# PIC32MK.net
KiCad netlist of a schematic drawn in Altium Designer
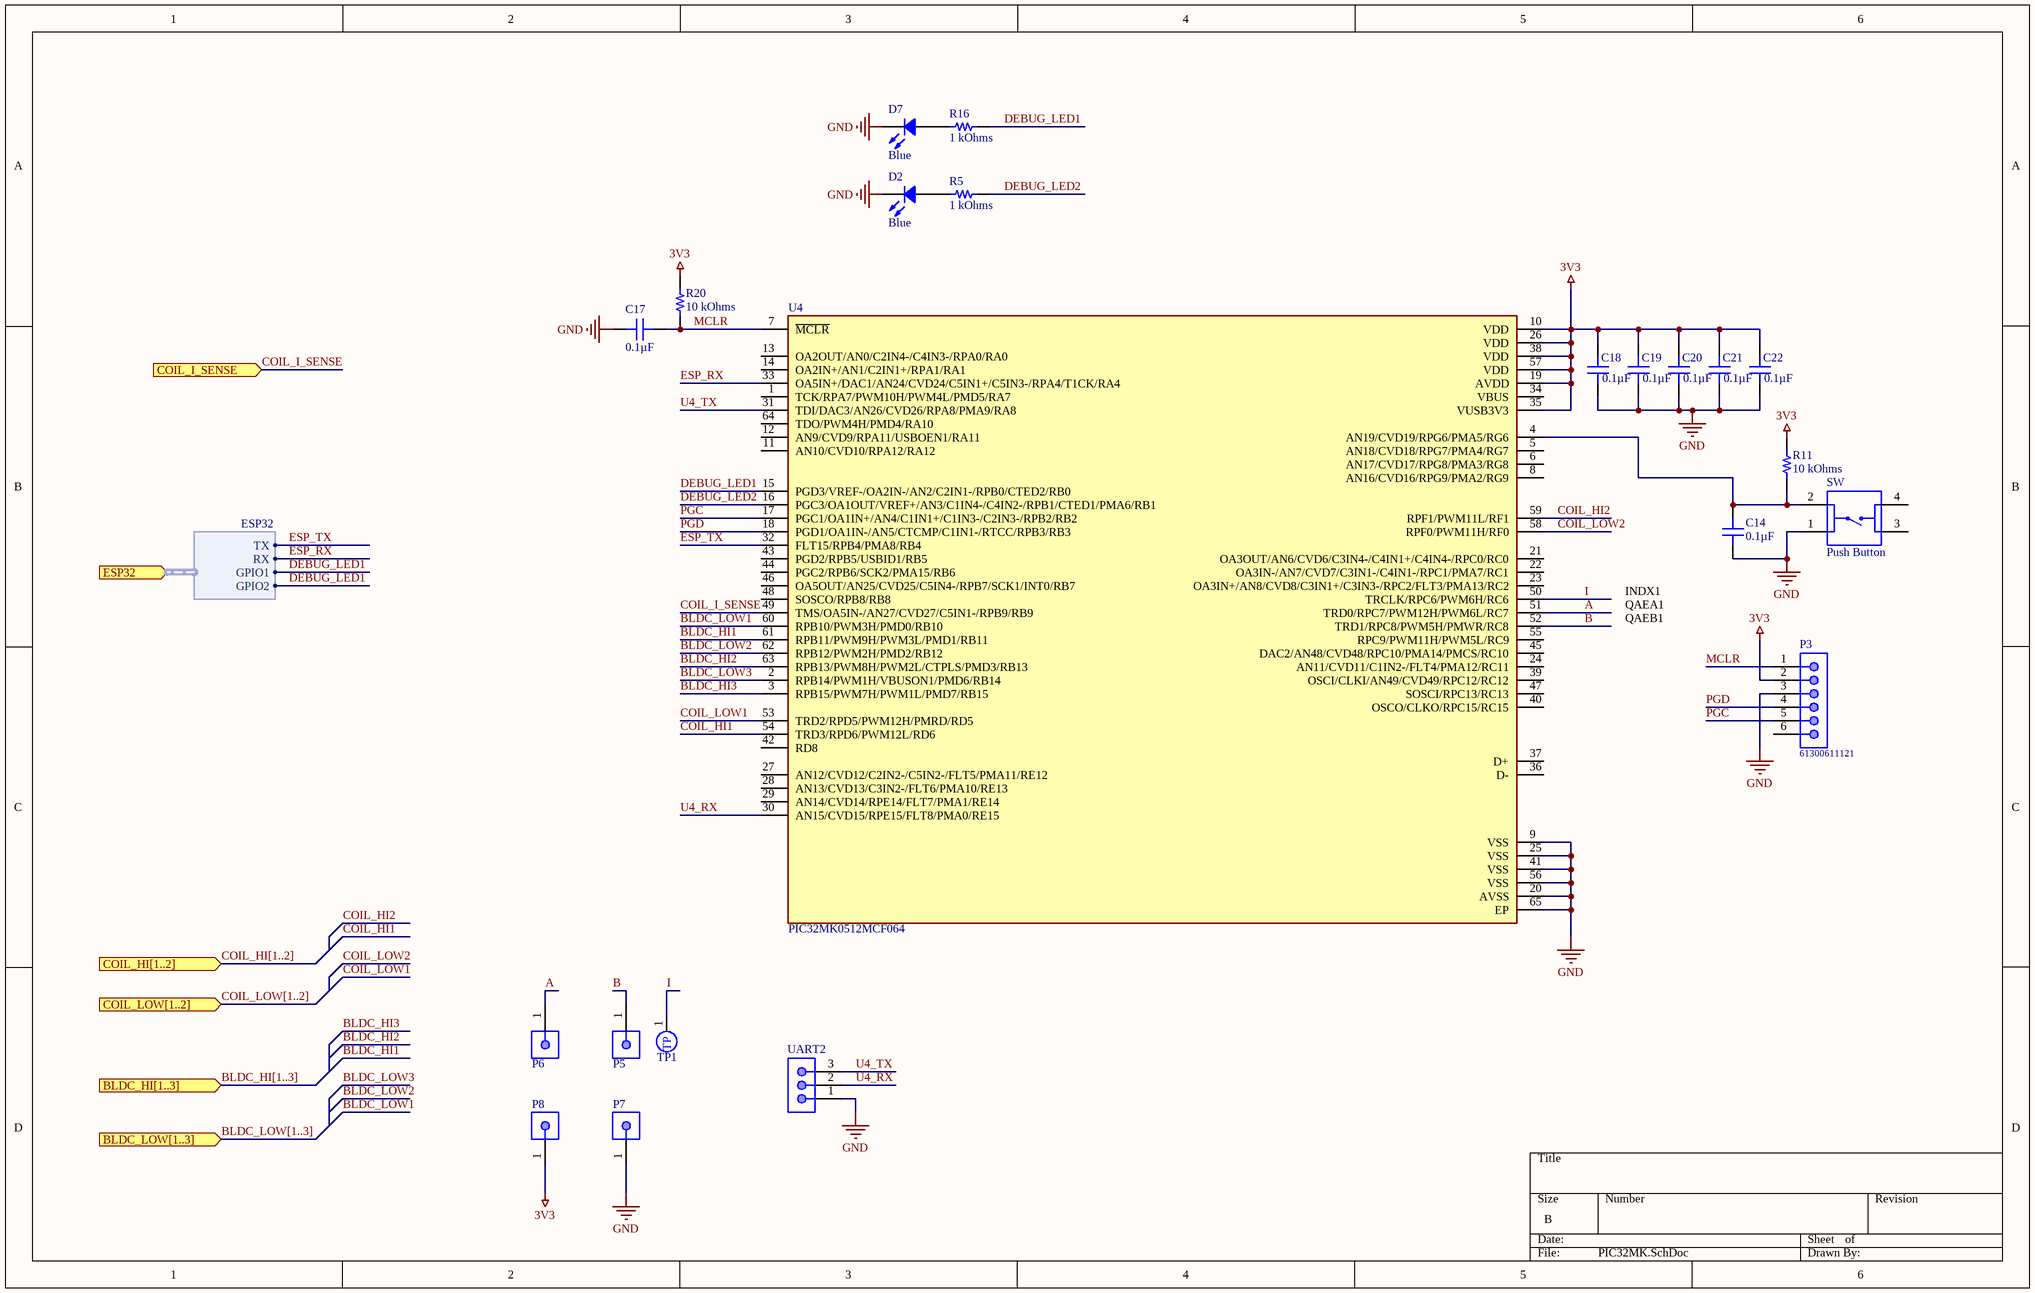
[diagram p0: PIC32MK.SchDoc]

(export (version "E")
  (design (tool "Eeschema 10.0.6"))
  (components
    (comp (ref "C14")
      (value "0.1µF")
      (footprint "CAP 0603_1608")
      (description "CAP CER 0.1UF 100V 0603 EPOXY")
      (fields
        (field (name "PART NUMBER") "GCG188R92A104KA03D")
        (field (name "MANUFACTURER") "Murata Electronics")
      )
      (libsource (lib "Celestial Altium Library - altium_library") (part "Capacitor"))
    )
    (comp (ref "C17")
      (value "0.1µF")
      (footprint "CAP 0603_1608")
      (description "CAP CER 0.1UF 100V 0603 EPOXY")
      (fields
        (field (name "PART NUMBER") "GCG188R92A104KA03D")
        (field (name "MANUFACTURER") "Murata Electronics")
      )
      (libsource (lib "Celestial Altium Library - altium_library") (part "Capacitor"))
    )
    (comp (ref "C18")
      (value "0.1µF")
      (footprint "CAP 0603_1608")
      (description "CAP CER 0.1UF 100V 0603 EPOXY")
      (fields
        (field (name "PART NUMBER") "GCG188R92A104KA03D")
        (field (name "MANUFACTURER") "Murata Electronics")
      )
      (libsource (lib "Celestial Altium Library - altium_library") (part "Capacitor"))
    )
    (comp (ref "C19")
      (value "0.1µF")
      (footprint "CAP 0603_1608")
      (description "CAP CER 0.1UF 100V 0603 EPOXY")
      (fields
        (field (name "PART NUMBER") "GCG188R92A104KA03D")
        (field (name "MANUFACTURER") "Murata Electronics")
      )
      (libsource (lib "Celestial Altium Library - altium_library") (part "Capacitor"))
    )
    (comp (ref "C20")
      (value "0.1µF")
      (footprint "CAP 0603_1608")
      (description "CAP CER 0.1UF 100V 0603 EPOXY")
      (fields
        (field (name "PART NUMBER") "GCG188R92A104KA03D")
        (field (name "MANUFACTURER") "Murata Electronics")
      )
      (libsource (lib "Celestial Altium Library - altium_library") (part "Capacitor"))
    )
    (comp (ref "C21")
      (value "0.1µF")
      (footprint "CAP 0603_1608")
      (description "CAP CER 0.1UF 100V 0603 EPOXY")
      (fields
        (field (name "PART NUMBER") "GCG188R92A104KA03D")
        (field (name "MANUFACTURER") "Murata Electronics")
      )
      (libsource (lib "Celestial Altium Library - altium_library") (part "Capacitor"))
    )
    (comp (ref "C22")
      (value "0.1µF")
      (footprint "CAP 0603_1608")
      (description "CAP CER 0.1UF 100V 0603 EPOXY")
      (fields
        (field (name "PART NUMBER") "GCG188R92A104KA03D")
        (field (name "MANUFACTURER") "Murata Electronics")
      )
      (libsource (lib "Celestial Altium Library - altium_library") (part "Capacitor"))
    )
    (comp (ref "D2")
      (value "Blue")
      (footprint "LED 0603_1608 GREEN")
      (description "Blue LED")
      (fields (field (name "PART NUMBER") "XZCDGK53W-8VF") (field (name "MANUFACTURER") "SunLED"))
      (libsource (lib "Celestial Altium Library - altium_library") (part "LED"))
    )
    (comp (ref "D7")
      (value "Blue")
      (footprint "LED 0603_1608 GREEN")
      (description "Blue LED")
      (fields (field (name "PART NUMBER") "XZCDGK53W-8VF") (field (name "MANUFACTURER") "SunLED"))
      (libsource (lib "Celestial Altium Library - altium_library") (part "LED"))
    )
    (comp (ref "P3")
      (value "61300611121")
      (footprint "61300611121")
      (description "WR-PHD Pin Header, THT, pitch 2.54mm, Single Row, Vertical, 6p")
      (fields (field (name "MANUFACTURER") "Wurth Elektronik"))
      (libsource (lib "Altium_WR-PHD") (part "61300611121"))
    )
    (comp (ref "P5")
      (value "61300111121")
      (footprint "61300111121")
      (description "WR-PHD Pin Header, THT, pitch 2.54mm, Single Row, Vertical, 1p")
      (fields (field (name "MANUFACTURER") "Wurth Elektronik"))
      (libsource (lib "Altium_WR-PHD") (part "61300111121"))
    )
    (comp (ref "P6")
      (value "61300111121")
      (footprint "61300111121")
      (description "WR-PHD Pin Header, THT, pitch 2.54mm, Single Row, Vertical, 1p")
      (fields (field (name "MANUFACTURER") "Wurth Elektronik"))
      (libsource (lib "Altium_WR-PHD") (part "61300111121"))
    )
    (comp (ref "P7")
      (value "61300111121")
      (footprint "61300111121")
      (description "WR-PHD Pin Header, THT, pitch 2.54mm, Single Row, Vertical, 1p")
      (fields (field (name "MANUFACTURER") "Wurth Elektronik"))
      (libsource (lib "Altium_WR-PHD") (part "61300111121"))
    )
    (comp (ref "P8")
      (value "61300111121")
      (footprint "61300111121")
      (description "WR-PHD Pin Header, THT, pitch 2.54mm, Single Row, Vertical, 1p")
      (fields (field (name "MANUFACTURER") "Wurth Elektronik"))
      (libsource (lib "Altium_WR-PHD") (part "61300111121"))
    )
    (comp (ref "R5")
      (value "1 kOhms")
      (footprint "RES 0603_1608")
      (description "RES 1K OHM 0.5% 1/10W 0603")
      (fields
        (field (name "PART NUMBER") "RNCF0603DTE1K00")
        (field (name "MANUFACTURER") "Stackpole Electronics Inc")
      )
      (libsource (lib "Celestial Altium Library - altium_library") (part "Resistor"))
    )
    (comp (ref "R11")
      (value "10 kOhms")
      (footprint "RES 0603_1608")
      (description "RES 10K OHM 0.1% 1/16W 0603")
      (fields
        (field (name "PART NUMBER") "RNCS0603BKE10K0")
        (field (name "MANUFACTURER") "Stackpole Electronics Inc")
      )
      (libsource (lib "Celestial Altium Library - altium_library") (part "Resistor"))
    )
    (comp (ref "R16")
      (value "1 kOhms")
      (footprint "RES 0603_1608")
      (description "RES 1K OHM 0.5% 1/10W 0603")
      (fields
        (field (name "PART NUMBER") "RNCF0603DTE1K00")
        (field (name "MANUFACTURER") "Stackpole Electronics Inc")
      )
      (libsource (lib "Celestial Altium Library - altium_library") (part "Resistor"))
    )
    (comp (ref "R20")
      (value "10 kOhms")
      (footprint "RES 0603_1608")
      (description "RES 10K OHM 0.1% 1/16W 0603")
      (fields
        (field (name "PART NUMBER") "RNCS0603BKE10K0")
        (field (name "MANUFACTURER") "Stackpole Electronics Inc")
      )
      (libsource (lib "Celestial Altium Library - altium_library") (part "Resistor"))
    )
    (comp (ref "SW")
      (value "Push Button")
      (footprint "PushButton")
      (description "50 mA SPST Round Actuator 160 Gram Force Tactile Pushbutton Switch")
      (fields (field (name "MP") "1825910-2") (field (name "MF") "TE Connectivity"))
      (libsource (lib "IC") (part "Push Button"))
    )
    (comp (ref "TP1")
      (value "TP")
      (footprint "TP")
      (description "Test point")
      (libsource (lib "IC") (part "TP"))
    )
    (comp (ref "U4")
      (value "PIC32MK0512MCF064")
      (footprint "QFN50P900X900X100-65N")
      (description "PIC32MK Microcontroller IC 32-Bit 120MHz 1MB _1M x 8_ FLASH 64-TQFP _10x10_")
      (fields
        (field (name "MP") "PIC32MK1024MCF064-I/PT")
        (field (name "DIGI-KEY_PART_NUMBER") "PIC32MK1024MCF064-I/PT-ND")
      )
      (libsource (lib "IC") (part "PIC32MK0512MCF064"))
    )
    (comp (ref "UART2")
      (value "3 pin 2mm JST Male")
      (footprint "3pin - 2mm header")
      (libsource (lib "IC") (part "3 pin 2mm JST Male"))
    )
  )
  (nets
    (net (code "2") (name "/A") (class "Default")
      (node (ref "P6") (pin "1") (pinfunction "1_1") (pintype "passive"))
      (node (ref "U4") (pin "51") (pinfunction "TRD0/RPC7/PWM12H/PWM6L/RC7_51") (pintype "passive"))
    )
    (net (code "3") (name "/B") (class "Default")
      (node (ref "P5") (pin "1") (pinfunction "1_1") (pintype "passive"))
      (node (ref "U4") (pin "52") (pinfunction "TRD1/RPC8/PWM5H/PMWR/RC8_52") (pintype "passive"))
    )
    (net (code "4") (name "/BLDC_HI1") (class "Default")
      (node (ref "U4") (pin "61") (pinfunction "RPB11/PWM9H/PWM3L/PMD1/RB11_61") (pintype "passive"))
    )
    (net (code "5") (name "/BLDC_HI2") (class "Default")
      (node (ref "U4") (pin "63") (pinfunction "RPB13/PWM8H/PWM2L/CTPLS/PMD3/RB13_63") (pintype "passive"))
    )
    (net (code "6") (name "/BLDC_HI3") (class "Default")
      (node (ref "U4") (pin "3") (pinfunction "RPB15/PWM7H/PWM1L/PMD7/RB15_3") (pintype "passive"))
    )
    (net (code "8") (name "/BLDC_LOW1") (class "Default")
      (node (ref "U4") (pin "60") (pinfunction "RPB10/PWM3H/PMD0/RB10_60") (pintype "passive"))
    )
    (net (code "9") (name "/BLDC_LOW2") (class "Default")
      (node (ref "U4") (pin "62") (pinfunction "RPB12/PWM2H/PMD2/RB12_62") (pintype "passive"))
    )
    (net (code "10") (name "/BLDC_LOW3") (class "Default")
      (node (ref "U4") (pin "2") (pinfunction "RPB14/PWM1H/VBUSON1/PMD6/RB14_2") (pintype "passive"))
    )
    (net (code "12") (name "/COIL_HI1") (class "Default")
      (node (ref "U4") (pin "54") (pinfunction "TRD3/RPD6/PWM12L/RD6_54") (pintype "passive"))
    )
    (net (code "13") (name "/COIL_HI2") (class "Default")
      (node (ref "U4") (pin "59") (pinfunction "RPF1/PWM11L/RF1_59") (pintype "passive"))
    )
    (net (code "15") (name "/COIL_I_SENSE") (class "Default")
      (node (ref "U4") (pin "49") (pinfunction "TMS/OA5IN-/AN27/CVD27/C5IN1-/RPB9/RB9_49") (pintype "passive"))
    )
    (net (code "16") (name "/COIL_LOW1") (class "Default")
      (node (ref "U4") (pin "53") (pinfunction "TRD2/RPD5/PWM12H/PMRD/RD5_53") (pintype "passive"))
    )
    (net (code "17") (name "/COIL_LOW2") (class "Default")
      (node (ref "U4") (pin "58") (pinfunction "RPF0/PWM11H/RF0_58") (pintype "passive"))
    )
    (net (code "19") (name "/DEBUG_LED1") (class "Default")
      (node (ref "R16") (pin "1") (pinfunction "1_1") (pintype "passive"))
      (node (ref "U4") (pin "15") (pinfunction "PGD3/VREF-/OA2IN-/AN2/C2IN1-/RPB0/CTED2/RB0_15") (pintype "passive"))
    )
    (net (code "20") (name "/DEBUG_LED2") (class "Default")
      (node (ref "R5") (pin "1") (pinfunction "1_1") (pintype "passive"))
      (node (ref "U4") (pin "16") (pinfunction "PGC3/OA1OUT/VREF+/AN3/C1IN4-/C4IN2-/RPB1/CTED1/PMA6/RB1_16") (pintype "passive"))
    )
    (net (code "21") (name "/ESP_RX") (class "Default")
      (node (ref "U4") (pin "33") (pinfunction "OA5IN+/DAC1/AN24/CVD24/C5IN1+/C5IN3-/RPA4/T1CK/RA4_33") (pintype "passive"))
    )
    (net (code "22") (name "/ESP_TX") (class "Default")
      (node (ref "U4") (pin "32") (pinfunction "FLT15/RPB4/PMA8/RB4_32") (pintype "passive"))
    )
    (net (code "23") (name "/I") (class "Default")
      (node (ref "TP1") (pin "1") (pinfunction "TP_1") (pintype "passive"))
      (node (ref "U4") (pin "50") (pinfunction "TRCLK/RPC6/PWM6H/RC6_50") (pintype "passive"))
    )
    (net (code "24") (name "/MCLR") (class "Default")
      (node (ref "C17") (pin "1") (pinfunction "1_1") (pintype "passive"))
      (node (ref "P3") (pin "1") (pinfunction "1_1") (pintype "passive"))
      (node (ref "R20") (pin "1") (pinfunction "1_1") (pintype "passive"))
      (node (ref "U4") (pin "7") (pinfunction "~{MCLR}_7") (pintype "passive"))
    )
    (net (code "25") (name "/PGC") (class "Default")
      (node (ref "P3") (pin "5") (pinfunction "5_5") (pintype "passive"))
      (node (ref "U4") (pin "17") (pinfunction "PGC1/OA1IN+/AN4/C1IN1+/C1IN3-/C2IN3-/RPB2/RB2_17") (pintype "passive"))
    )
    (net (code "26") (name "/PGD") (class "Default")
      (node (ref "P3") (pin "4") (pinfunction "4_4") (pintype "passive"))
      (node (ref "U4") (pin "18") (pinfunction "PGD1/OA1IN-/AN5/CTCMP/C1IN1-/RTCC/RPB3/RB3_18") (pintype "passive"))
    )
    (net (code "27") (name "/U4_RX") (class "Default")
      (node (ref "U4") (pin "30") (pinfunction "AN15/CVD15/RPE15/FLT8/PMA0/RE15_30") (pintype "passive"))
      (node (ref "UART2") (pin "2") (pinfunction "2_2") (pintype "passive"))
    )
    (net (code "28") (name "/U4_TX") (class "Default")
      (node (ref "U4") (pin "31") (pinfunction "TDI/DAC3/AN26/CVD26/RPA8/PMA9/RA8_31") (pintype "passive"))
      (node (ref "UART2") (pin "3") (pinfunction "3_3") (pintype "passive"))
    )
    (net (code "30") (name "3V3") (class "Default")
      (node (ref "C18") (pin "1") (pinfunction "1_1") (pintype "passive"))
      (node (ref "C19") (pin "1") (pinfunction "1_1") (pintype "passive"))
      (node (ref "C20") (pin "1") (pinfunction "1_1") (pintype "passive"))
      (node (ref "C21") (pin "1") (pinfunction "1_1") (pintype "passive"))
      (node (ref "C22") (pin "1") (pinfunction "1_1") (pintype "passive"))
      (node (ref "P3") (pin "2") (pinfunction "2_2") (pintype "passive"))
      (node (ref "P8") (pin "1") (pinfunction "1_1") (pintype "passive"))
      (node (ref "R11") (pin "2") (pinfunction "2_2") (pintype "passive"))
      (node (ref "R20") (pin "2") (pinfunction "2_2") (pintype "passive"))
      (node (ref "U4") (pin "10") (pinfunction "VDD_10") (pintype "power_in"))
      (node (ref "U4") (pin "19") (pinfunction "AVDD_19") (pintype "power_in"))
      (node (ref "U4") (pin "26") (pinfunction "VDD_26") (pintype "power_in"))
      (node (ref "U4") (pin "35") (pinfunction "VUSB3V3_35") (pintype "passive"))
      (node (ref "U4") (pin "38") (pinfunction "VDD_38") (pintype "power_in"))
      (node (ref "U4") (pin "57") (pinfunction "VDD_57") (pintype "power_in"))
    )
    (net (code "31") (name "GND") (class "Default")
      (node (ref "C14") (pin "2") (pinfunction "2_2") (pintype "passive"))
      (node (ref "C17") (pin "2") (pinfunction "2_2") (pintype "passive"))
      (node (ref "C18") (pin "2") (pinfunction "2_2") (pintype "passive"))
      (node (ref "C19") (pin "2") (pinfunction "2_2") (pintype "passive"))
      (node (ref "C20") (pin "2") (pinfunction "2_2") (pintype "passive"))
      (node (ref "C21") (pin "2") (pinfunction "2_2") (pintype "passive"))
      (node (ref "C22") (pin "2") (pinfunction "2_2") (pintype "passive"))
      (node (ref "D2") (pin "2") (pinfunction "2_2") (pintype "passive"))
      (node (ref "D7") (pin "2") (pinfunction "2_2") (pintype "passive"))
      (node (ref "P3") (pin "3") (pinfunction "3_3") (pintype "passive"))
      (node (ref "P7") (pin "1") (pinfunction "1_1") (pintype "passive"))
      (node (ref "SW") (pin "1") (pinfunction "1_1") (pintype "passive"))
      (node (ref "U4") (pin "20") (pinfunction "AVSS_20") (pintype "power_in"))
      (node (ref "U4") (pin "25") (pinfunction "VSS_25") (pintype "power_in"))
      (node (ref "U4") (pin "41") (pinfunction "VSS_41") (pintype "power_in"))
      (node (ref "U4") (pin "56") (pinfunction "VSS_56") (pintype "power_in"))
      (node (ref "U4") (pin "65") (pinfunction "EP_65") (pintype "power_in"))
      (node (ref "U4") (pin "9") (pinfunction "VSS_9") (pintype "power_in"))
      (node (ref "UART2") (pin "1") (pinfunction "1_1") (pintype "passive"))
    )
    (net (code "32") (name "Net-(D2-Pad1)") (class "Default")
      (node (ref "D2") (pin "1") (pinfunction "1_1") (pintype "passive"))
      (node (ref "R5") (pin "2") (pinfunction "2_2") (pintype "passive"))
    )
    (net (code "33") (name "Net-(D7-Pad1)") (class "Default")
      (node (ref "D7") (pin "1") (pinfunction "1_1") (pintype "passive"))
      (node (ref "R16") (pin "2") (pinfunction "2_2") (pintype "passive"))
    )
    (net (code "34") (name "Net-(U4-AN19{slash}CVD19{slash}RPG6{slash}PMA5{slash}RG6)") (class "Default")
      (node (ref "C14") (pin "1") (pinfunction "1_1") (pintype "passive"))
      (node (ref "R11") (pin "1") (pinfunction "1_1") (pintype "passive"))
      (node (ref "SW") (pin "2") (pinfunction "2_2") (pintype "passive"))
      (node (ref "U4") (pin "4") (pinfunction "AN19/CVD19/RPG6/PMA5/RG6_4") (pintype "passive"))
    )
    (net (code "35") (name "unconnected-(P3-Pad6)") (class "Default")
      (node (ref "P3") (pin "6") (pinfunction "6_6") (pintype "passive"))
    )
    (net (code "36") (name "unconnected-(SW-Pad3)") (class "Default")
      (node (ref "SW") (pin "3") (pinfunction "3_3") (pintype "passive"))
    )
    (net (code "37") (name "unconnected-(SW-Pad4)") (class "Default")
      (node (ref "SW") (pin "4") (pinfunction "4_4") (pintype "passive"))
    )
    (net (code "38") (name "unconnected-(U4-AN9{slash}CVD9{slash}RPA11{slash}USBOEN1{slash}RA11-Pad12)") (class "Default")
      (node (ref "U4") (pin "12") (pinfunction "AN9/CVD9/RPA11/USBOEN1/RA11_12") (pintype "passive"))
    )
    (net (code "39") (name "unconnected-(U4-AN10{slash}CVD10{slash}RPA12{slash}RA12-Pad11)") (class "Default")
      (node (ref "U4") (pin "11") (pinfunction "AN10/CVD10/RPA12/RA12_11") (pintype "passive"))
    )
    (net (code "40") (name "unconnected-(U4-AN11{slash}CVD11{slash}C1IN2-{slash}FLT4{slash}PMA12{slash}RC11-Pad24)") (class "Default")
      (node (ref "U4") (pin "24") (pinfunction "AN11/CVD11/C1IN2-/FLT4/PMA12/RC11_24") (pintype "passive"))
    )
    (net (code "41") (name "unconnected-(U4-AN12{slash}CVD12{slash}C2IN2-{slash}C5IN2-{slash}FLT5{slash}PMA11{slash}RE12-Pad27)") (class "Default")
      (node (ref "U4") (pin "27") (pinfunction "AN12/CVD12/C2IN2-/C5IN2-/FLT5/PMA11/RE12_27") (pintype "passive"))
    )
    (net (code "42") (name "unconnected-(U4-AN13{slash}CVD13{slash}C3IN2-{slash}FLT6{slash}PMA10{slash}RE13-Pad28)") (class "Default")
      (node (ref "U4") (pin "28") (pinfunction "AN13/CVD13/C3IN2-/FLT6/PMA10/RE13_28") (pintype "passive"))
    )
    (net (code "43") (name "unconnected-(U4-AN14{slash}CVD14{slash}RPE14{slash}FLT7{slash}PMA1{slash}RE14-Pad29)") (class "Default")
      (node (ref "U4") (pin "29") (pinfunction "AN14/CVD14/RPE14/FLT7/PMA1/RE14_29") (pintype "passive"))
    )
    (net (code "44") (name "unconnected-(U4-AN16{slash}CVD16{slash}RPG9{slash}PMA2{slash}RG9-Pad8)") (class "Default")
      (node (ref "U4") (pin "8") (pinfunction "AN16/CVD16/RPG9/PMA2/RG9_8") (pintype "passive"))
    )
    (net (code "45") (name "unconnected-(U4-AN17{slash}CVD17{slash}RPG8{slash}PMA3{slash}RG8-Pad6)") (class "Default")
      (node (ref "U4") (pin "6") (pinfunction "AN17/CVD17/RPG8/PMA3/RG8_6") (pintype "passive"))
    )
    (net (code "46") (name "unconnected-(U4-AN18{slash}CVD18{slash}RPG7{slash}PMA4{slash}RG7-Pad5)") (class "Default")
      (node (ref "U4") (pin "5") (pinfunction "AN18/CVD18/RPG7/PMA4/RG7_5") (pintype "passive"))
    )
    (net (code "47") (name "unconnected-(U4-D+-Pad37)") (class "Default")
      (node (ref "U4") (pin "37") (pinfunction "D+_37") (pintype "passive"))
    )
    (net (code "48") (name "unconnected-(U4-D--Pad36)") (class "Default")
      (node (ref "U4") (pin "36") (pinfunction "D-_36") (pintype "passive"))
    )
    (net (code "49") (name "unconnected-(U4-DAC2{slash}AN48{slash}CVD48{slash}RPC10{slash}PMA14{slash}PMCS{slash}RC10-Pad45)") (class "Default")
      (node (ref "U4") (pin "45") (pinfunction "DAC2/AN48/CVD48/RPC10/PMA14/PMCS/RC10_45") (pintype "passive"))
    )
    (net (code "50") (name "unconnected-(U4-OA2IN+{slash}AN1{slash}C2IN1+{slash}RPA1{slash}RA1-Pad14)") (class "Default")
      (node (ref "U4") (pin "14") (pinfunction "OA2IN+/AN1/C2IN1+/RPA1/RA1_14") (pintype "passive"))
    )
    (net (code "51") (name "unconnected-(U4-OA2OUT{slash}AN0{slash}C2IN4-{slash}C4IN3-{slash}RPA0{slash}RA0-Pad13)") (class "Default")
      (node (ref "U4") (pin "13") (pinfunction "OA2OUT/AN0/C2IN4-/C4IN3-/RPA0/RA0_13") (pintype "passive"))
    )
    (net (code "52") (name "unconnected-(U4-OA3IN+{slash}AN8{slash}CVD8{slash}C3IN1+{slash}C3IN3-{slash}RPC2{slash}FLT3{slash}PMA13{slash}RC2-Pad23)") (class "Default")
      (node (ref "U4") (pin "23") (pinfunction "OA3IN+/AN8/CVD8/C3IN1+/C3IN3-/RPC2/FLT3/PMA13/RC2_23") (pintype "passive"))
    )
    (net (code "53") (name "unconnected-(U4-OA3IN-{slash}AN7{slash}CVD7{slash}C3IN1-{slash}C4IN1-{slash}RPC1{slash}PMA7{slash}RC1-Pad22)") (class "Default")
      (node (ref "U4") (pin "22") (pinfunction "OA3IN-/AN7/CVD7/C3IN1-/C4IN1-/RPC1/PMA7/RC1_22") (pintype "passive"))
    )
    (net (code "54") (name "unconnected-(U4-OA3OUT{slash}AN6{slash}CVD6{slash}C3IN4-{slash}C4IN1+{slash}C4IN4-{slash}RPC0{slash}RC0-Pad21)") (class "Default")
      (node (ref "U4") (pin "21") (pinfunction "OA3OUT/AN6/CVD6/C3IN4-/C4IN1+/C4IN4-/RPC0/RC0_21") (pintype "passive"))
    )
    (net (code "55") (name "unconnected-(U4-OA5OUT{slash}AN25{slash}CVD25{slash}C5IN4-{slash}RPB7{slash}SCK1{slash}INT0{slash}RB7-Pad46)") (class "Default")
      (node (ref "U4") (pin "46") (pinfunction "OA5OUT/AN25/CVD25/C5IN4-/RPB7/SCK1/INT0/RB7_46") (pintype "passive"))
    )
    (net (code "56") (name "unconnected-(U4-OSCI{slash}CLKI{slash}AN49{slash}CVD49{slash}RPC12{slash}RC12-Pad39)") (class "Default")
      (node (ref "U4") (pin "39") (pinfunction "OSCI/CLKI/AN49/CVD49/RPC12/RC12_39") (pintype "passive"))
    )
    (net (code "57") (name "unconnected-(U4-OSCO{slash}CLKO{slash}RPC15{slash}RC15-Pad40)") (class "Default")
      (node (ref "U4") (pin "40") (pinfunction "OSCO/CLKO/RPC15/RC15_40") (pintype "passive"))
    )
    (net (code "58") (name "unconnected-(U4-PGC2{slash}RPB6{slash}SCK2{slash}PMA15{slash}RB6-Pad44)") (class "Default")
      (node (ref "U4") (pin "44") (pinfunction "PGC2/RPB6/SCK2/PMA15/RB6_44") (pintype "passive"))
    )
    (net (code "59") (name "unconnected-(U4-PGD2{slash}RPB5{slash}USBID1{slash}RB5-Pad43)") (class "Default")
      (node (ref "U4") (pin "43") (pinfunction "PGD2/RPB5/USBID1/RB5_43") (pintype "passive"))
    )
    (net (code "60") (name "unconnected-(U4-RD8-Pad42)") (class "Default")
      (node (ref "U4") (pin "42") (pinfunction "RD8_42") (pintype "passive"))
    )
    (net (code "61") (name "unconnected-(U4-RPC9{slash}PWM11H{slash}PWM5L{slash}RC9-Pad55)") (class "Default")
      (node (ref "U4") (pin "55") (pinfunction "RPC9/PWM11H/PWM5L/RC9_55") (pintype "passive"))
    )
    (net (code "62") (name "unconnected-(U4-SOSCI{slash}RPC13{slash}RC13-Pad47)") (class "Default")
      (node (ref "U4") (pin "47") (pinfunction "SOSCI/RPC13/RC13_47") (pintype "passive"))
    )
    (net (code "63") (name "unconnected-(U4-SOSCO{slash}RPB8{slash}RB8-Pad48)") (class "Default")
      (node (ref "U4") (pin "48") (pinfunction "SOSCO/RPB8/RB8_48") (pintype "passive"))
    )
    (net (code "64") (name "unconnected-(U4-TCK{slash}RPA7{slash}PWM10H{slash}PWM4L{slash}PMD5{slash}RA7-Pad1)") (class "Default")
      (node (ref "U4") (pin "1") (pinfunction "TCK/RPA7/PWM10H/PWM4L/PMD5/RA7_1") (pintype "passive"))
    )
    (net (code "65") (name "unconnected-(U4-TDO{slash}PWM4H{slash}PMD4{slash}RA10-Pad64)") (class "Default")
      (node (ref "U4") (pin "64") (pinfunction "TDO/PWM4H/PMD4/RA10_64") (pintype "passive"))
    )
    (net (code "66") (name "unconnected-(U4-VBUS-Pad34)") (class "Default")
      (node (ref "U4") (pin "34") (pinfunction "VBUS_34") (pintype "power_in"))
    )
  )
)
